# 03-Gate_Driver.net
KiCad netlist of a schematic drawn in Altium Designer
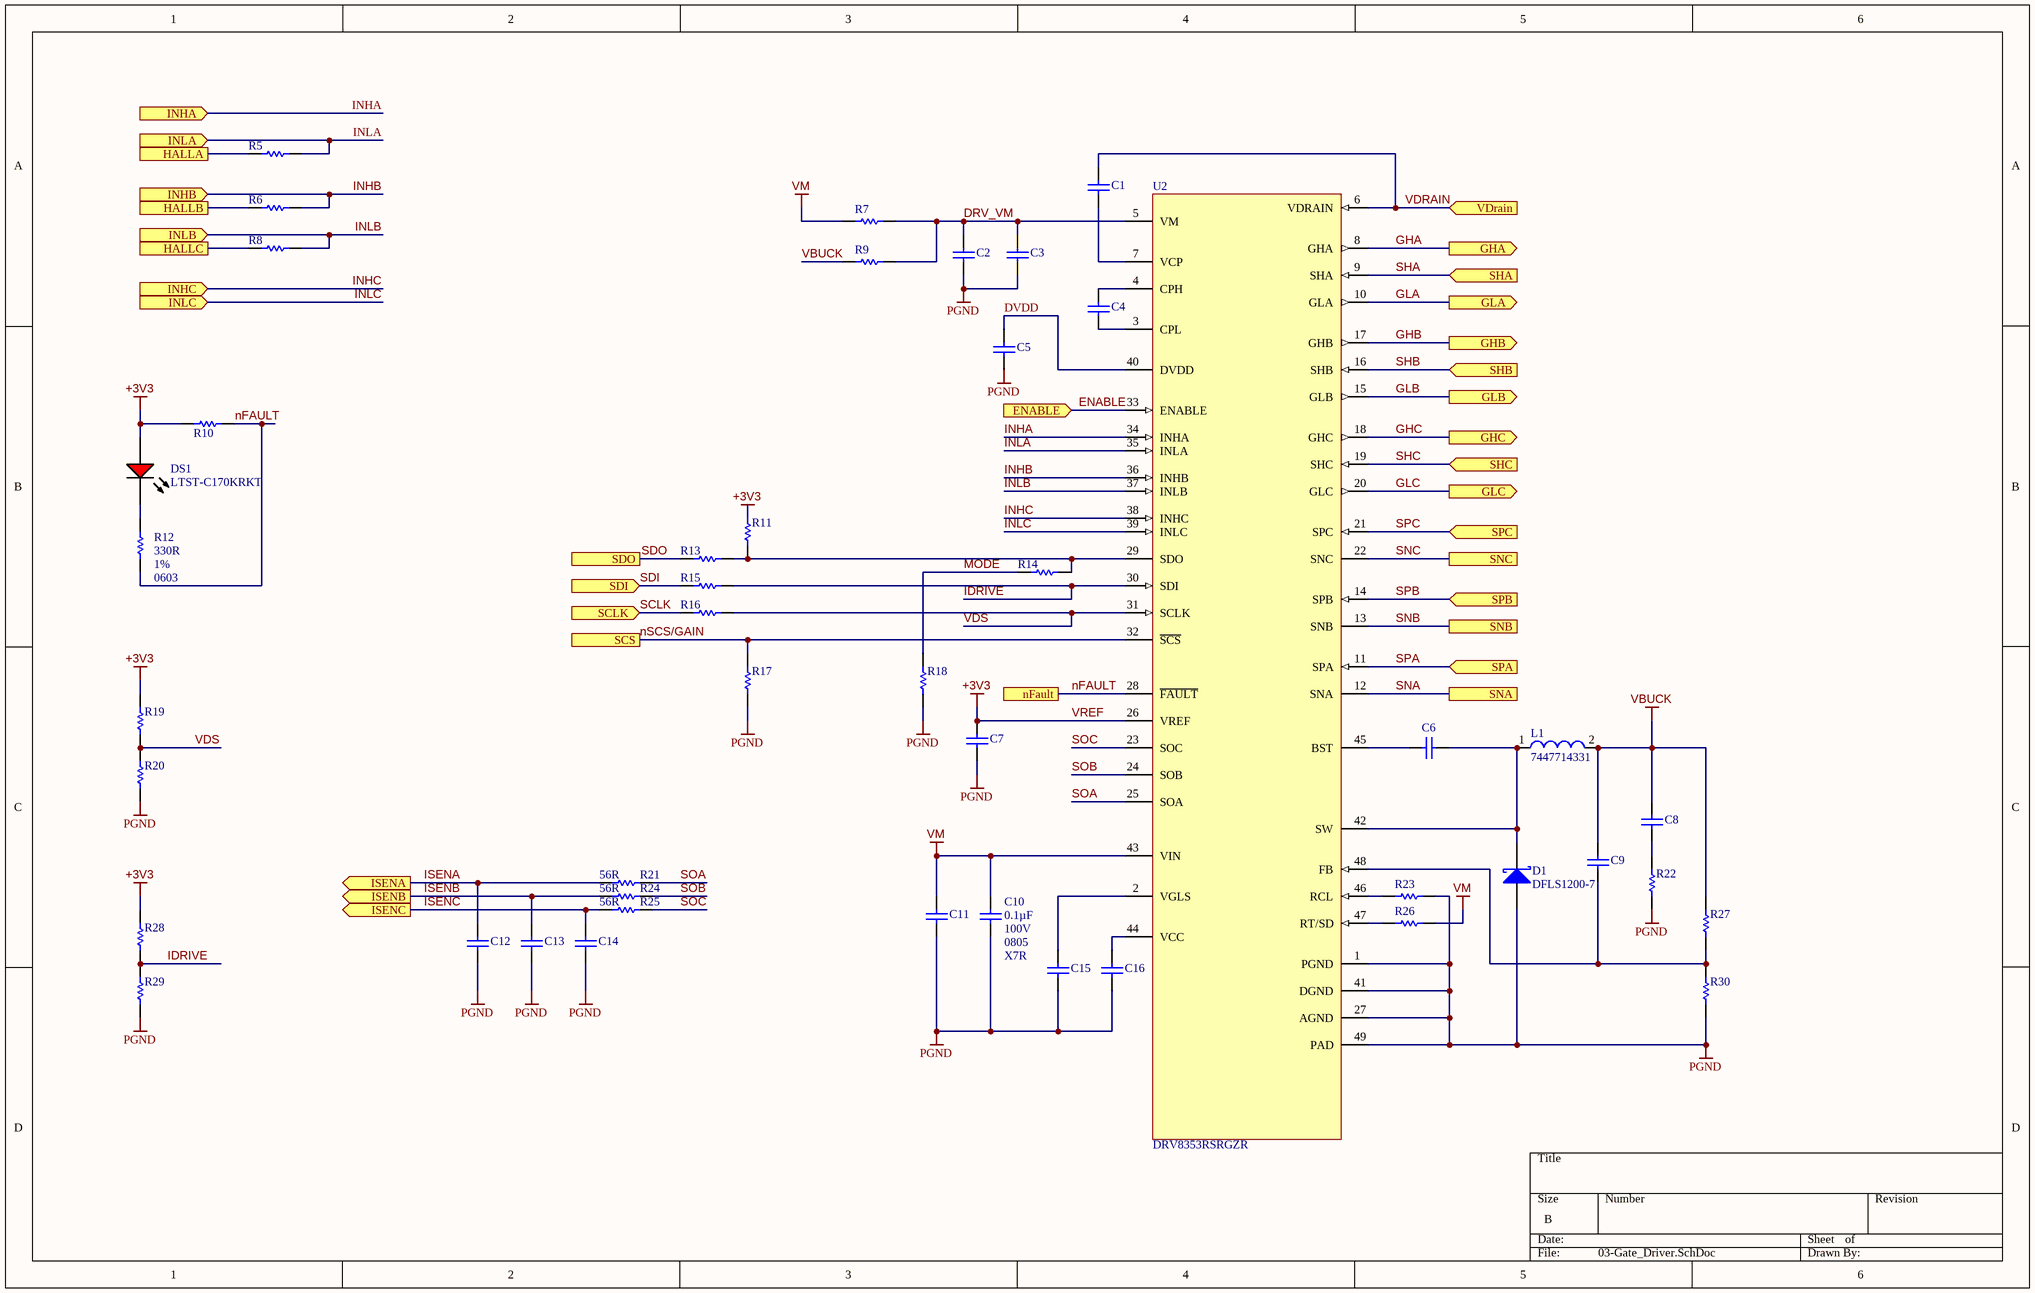
[diagram p0: 03-Gate_Driver.SchDoc]

(export (version "E")
  (design (tool "Eeschema 10.0.6"))
  (components
    (comp (ref "C1")
      (value "GRM31CR72A105KA01L")
      (footprint "CAPC3216X180X55ML20T25")
      (description "Chip Capacitor, 1 uF, +/- 10%, 100 V, -55 to 125 degC, 1206 (3216 Metric), RoHS, Tape and Reel")
      (fields (field (name "TOLERANCE") "±10%") (field (name "MANUFACTURER") "Murata"))
      (libsource (lib "Altium Content Vault") (part "CAP-NP-2"))
    )
    (comp (ref "C2")
      (value "C5750X7S2A106M230KB")
      (footprint "TDK-C5750-2_L")
      (description "Chip Capacitor, 10 uF, +/- 20%, 100 V, -55 to 125 degC, 2220 (5750 Metric), RoHS, Tape and Reel")
      (fields
        (field (name "PCN PART NUMBER") "MLCCPartNumberChange30/Nov/2012")
        (field (name "MANUFACTURER") "TDK")
      )
      (libsource (lib "Altium Content Vault") (part "CAP-NP-2"))
    )
    (comp (ref "C3")
      (value "C2012X7R2A104K125AA")
      (footprint "CAPC2013X145X20ML20")
      (description "Chip Capacitor, 100 nF, +/- 10%, 100 V, -55 to 1255 degC, 0805 (2012 Metric), RoHS, Tape and Reel")
      (fields (field (name "MANUFACTURER") "TDK") (field (name "TOLERANCE") "±10%"))
      (libsource (lib "Altium Content Vault") (part "CAP-NP-2"))
    )
    (comp (ref "C4")
      (value "C0805C473K1RACTU")
      (footprint "CAPC2013X110X50LL20T25")
      (fields (field (name "MANUFACTURER") "Kemet"))
      (libsource (lib "Altium Content Vault") (part "CAP"))
    )
    (comp (ref "C5")
      (value "C0603C105K4RACTU")
      (footprint "CAPC1608X90X35LL15T15")
      (fields (field (name "MANUFACTURER") "Kemet"))
      (libsource (lib "Altium Content Vault") (part "CAP"))
    )
    (comp (ref "C6")
      (value "C0603C103K4RACTU")
      (footprint "CAPC1608X87X35ML15T15")
      (fields (field (name "MANUFACTURER") "Kemet"))
      (libsource (lib "Altium Content Vault") (part "CAP"))
    )
    (comp (ref "C7")
      (value "C0603C104J4RACTU")
      (footprint "CAPC1608X87X35NL15T15")
      (fields (field (name "MANUFACTURER") "Kemet"))
      (libsource (lib "Altium Content Vault") (part "CAP"))
    )
    (comp (ref "C8")
      (value "C2012X7R1H225K125AC")
      (footprint "CAPC2013X145X20LL20")
      (description "Chip Capacitor, 2.2 uF, +/- 10%, 50 V, -55 to 125 degC, 0805 (2012 Metric), RoHS, Tape and Reel")
      (fields (field (name "MANUFACTURER") "TDK") (field (name "TOLERANCE") "±10%"))
      (libsource (lib "Altium Content Vault") (part "CAP-NP-2"))
    )
    (comp (ref "C9")
      (value "GRM1885C1H362JA01D")
      (footprint "CAPC1608X90X35ML10T15")
      (fields (field (name "MANUFACTURER") "Murata"))
      (libsource (lib "Altium Content Vault") (part "CAP"))
    )
    (comp (ref "C10")
      (value "C2012X7R2A104K125AA")
      (footprint "CAPC2013X145X20ML20")
      (description "Chip Capacitor, 100 nF, +/- 10%, 100 V, -55 to 1255 degC, 0805 (2012 Metric), RoHS, Tape and Reel")
      (fields
        (field (name "TEMPERATURE COEFFICIENT") "X7R")
        (field (name "MANUFACTURER") "TDK")
        (field (name "VOLTAGE - RATED") "100V")
        (field (name "TOLERANCE") "±10%")
        (field (name "PACKAGE REFERENCE") "0805")
        (field (name "CAPACITANCE") "0.1µF")
      )
      (libsource (lib "Altium Content Vault") (part "CAP-NP-2"))
    )
    (comp (ref "C11")
      (value "C3216X7R2A105K160AA")
      (footprint "CAPC3216X180X20LL20")
      (description "Chip Capacitor, 1 uF, +/- 10%, 100 V, -55 to 125 degC, 1206 (3216 Metric), RoHS, Tape and Reel")
      (fields (field (name "MANUFACTURER") "TDK") (field (name "TOLERANCE") "±10%"))
      (libsource (lib "Altium Content Vault") (part "CAP-NP-2"))
    )
    (comp (ref "C12")
      (value "GRM188R71C222KA01D")
      (footprint "CAPC1608X90X35NL10T15")
      (fields (field (name "MANUFACTURER") "Murata"))
      (libsource (lib "Altium Content Vault") (part "CAP"))
    )
    (comp (ref "C13")
      (value "GRM188R71C222KA01D")
      (footprint "CAPC1608X90X35NL10T15")
      (fields (field (name "MANUFACTURER") "Murata"))
      (libsource (lib "Altium Content Vault") (part "CAP"))
    )
    (comp (ref "C14")
      (value "GRM188R71C222KA01D")
      (footprint "CAPC1608X90X35NL10T15")
      (fields (field (name "MANUFACTURER") "Murata"))
      (libsource (lib "Altium Content Vault") (part "CAP"))
    )
    (comp (ref "C15")
      (value "C0805C105K3RACTU")
      (footprint "CAPC2013X140X50LL20T25")
      (fields (field (name "MANUFACTURER") "Kemet"))
      (libsource (lib "Altium Content Vault") (part "CAP"))
    )
    (comp (ref "C16")
      (value "C0603C105K4RACTU")
      (footprint "CAPC1608X90X35LL15T15")
      (fields (field (name "MANUFACTURER") "Kemet"))
      (libsource (lib "Altium Content Vault") (part "CAP"))
    )
    (comp (ref "D1")
      (value "DFLS1200-7")
      (footprint "DIOD-POWERDI123-2_A_V")
      (fields (field (name "MANUFACTURER") "Diodes Inc"))
      (libsource (lib "Altium Content Vault") (part "DSKY-AK-2"))
    )
    (comp (ref "DS1")
      (value "LTST-C170KRKT")
      (footprint "LTST-C170KRKT_V")
      (description "LED Red, 75 mW, 54 mcd, -55 to 85 degC, 2-Pin SMD, RoHS, Tape and Reel")
      (fields (field (name "MANUFACTURER") "Lite-On"))
      (libsource (lib "Altium Content Vault") (part "LED-RED-AK-2"))
    )
    (comp (ref "L1")
      (value "7447714331")
      (footprint "WE-PD 1050")
      (description "SMD-Shielded Power Inductor WE-PD, L=330 µH")
      (fields (field (name "MANUFACTURER") "Wuerth Elektronik"))
      (libsource (lib "Altium Content Vault") (part "PAS-IND-INDUCTOR-2"))
    )
    (comp (ref "R5")
      (value "ERJ-3GEY0R00V")
      (footprint "RESC1608X55X30NL15T15")
      (fields (field (name "MANUFACTURER") "Panasonic"))
      (libsource (lib "Altium Content Vault") (part "RES"))
    )
    (comp (ref "R6")
      (value "ERJ-3GEY0R00V")
      (footprint "RESC1608X55X30NL15T15")
      (fields (field (name "MANUFACTURER") "Panasonic"))
      (libsource (lib "Altium Content Vault") (part "RES"))
    )
    (comp (ref "R7")
      (value "ERJ-3GEY0R00V")
      (footprint "RESC1608X55X30NL15T15")
      (fields (field (name "MANUFACTURER") "Panasonic"))
      (libsource (lib "Altium Content Vault") (part "RES"))
    )
    (comp (ref "R8")
      (value "ERJ-3GEY0R00V")
      (footprint "RESC1608X55X30NL15T15")
      (fields (field (name "MANUFACTURER") "Panasonic"))
      (libsource (lib "Altium Content Vault") (part "RES"))
    )
    (comp (ref "R9")
      (value "ERJ-3GEY0R00V")
      (footprint "RESC1608X55X30NL15T15")
      (fields (field (name "MANUFACTURER") "Panasonic"))
      (libsource (lib "Altium Content Vault") (part "RES"))
    )
    (comp (ref "R10")
      (value "RG1608P-103-B-T5")
      (footprint "RESC1608X50X30NL20T20")
      (fields (field (name "MANUFACTURER") "Susumu"))
      (libsource (lib "Altium Content Vault") (part "RES"))
    )
    (comp (ref "R11")
      (value "ERJ-3GEYJ102V")
      (footprint "RESC1608X55X30ML15T15")
      (fields (field (name "MANUFACTURER") "Panasonic"))
      (libsource (lib "Altium Content Vault") (part "RES"))
    )
    (comp (ref "R12")
      (value "ERJ3EKF3300V")
      (footprint "RESC1608X55X30NL15T15")
      (fields
        (field (name "MANUFACTURER") "Panasonic")
        (field (name "CASE CODE (IMPERIAL)") "0603")
        (field (name "TOLERANCE") "1%")
        (field (name "RESISTANCE") "330R")
      )
      (libsource (lib "Altium Content Vault") (part "RES"))
    )
    (comp (ref "R13")
      (value "ERJ-3GEY0R00V")
      (footprint "RESC1608X55X30NL15T15")
      (fields (field (name "MANUFACTURER") "Panasonic"))
      (libsource (lib "Altium Content Vault") (part "RES"))
    )
    (comp (ref "R14")
      (value "ERJ-3GEY0R00V")
      (footprint "RESC1608X55X30NL15T15")
      (fields (field (name "MANUFACTURER") "Panasonic"))
      (libsource (lib "Altium Content Vault") (part "RES"))
    )
    (comp (ref "R15")
      (value "ERJ-3GEY0R00V")
      (footprint "RESC1608X55X30NL15T15")
      (fields (field (name "MANUFACTURER") "Panasonic"))
      (libsource (lib "Altium Content Vault") (part "RES"))
    )
    (comp (ref "R16")
      (value "ERJ-3GEY0R00V")
      (footprint "RESC1608X55X30NL15T15")
      (fields (field (name "MANUFACTURER") "Panasonic"))
      (libsource (lib "Altium Content Vault") (part "RES"))
    )
    (comp (ref "R17")
      (value "CRCW060347K0JNEA")
      (footprint "RESC1609X50X30ML10T20")
      (fields (field (name "MANUFACTURER") "Vishay Dale"))
      (libsource (lib "Altium Content Vault") (part "RES"))
    )
    (comp (ref "R18")
      (value "CRCW060347K0JNEA")
      (footprint "RESC1609X50X30ML10T20")
      (fields (field (name "MANUFACTURER") "Vishay Dale"))
      (libsource (lib "Altium Content Vault") (part "RES"))
    )
    (comp (ref "R19")
      (value "CRCW060375K0JNEA")
      (footprint "RESC1609X50X30ML10T20")
      (fields (field (name "MANUFACTURER") "Vishay Dale"))
      (libsource (lib "Altium Content Vault") (part "RES"))
    )
    (comp (ref "R20")
      (value "CRCW060375K0JNEA")
      (footprint "RESC1609X50X30ML10T20")
      (fields (field (name "MANUFACTURER") "Vishay Dale"))
      (libsource (lib "Altium Content Vault") (part "RES"))
    )
    (comp (ref "R21")
      (value "CRCW060356R0FKEA")
      (footprint "RESC1609X50X30ML10T20")
      (fields
        (field (name "MANUFACTURER") "Vishay Dale")
        (field (name "TOLERANCE") "1%")
        (field (name "RESISTANCE") "56R")
      )
      (libsource (lib "Altium Content Vault") (part "RES"))
    )
    (comp (ref "R22")
      (value "2R61 1% 0603(1608)")
      (footprint "RESC0603(1608)_N")
      (description "2R61 0.1W 1% 0603 (1608 Metric)  SMD")
      (fields (field (name "POWER") "0.1 W") (field (name "TOLERANCE") "1 %"))
      (libsource (lib "Altium Content Vault") (part "RES"))
    )
    (comp (ref "R23")
      (value "CRCW0603107KFKEA")
      (footprint "RESC1609X50X30LL10T20")
      (fields (field (name "MANUFACTURER") "Vishay Dale"))
      (libsource (lib "Altium Content Vault") (part "RES"))
    )
    (comp (ref "R24")
      (value "CRCW060356R0FKEA")
      (footprint "RESC1609X50X30ML10T20")
      (fields
        (field (name "MANUFACTURER") "Vishay Dale")
        (field (name "TOLERANCE") "1%")
        (field (name "RESISTANCE") "56R")
      )
      (libsource (lib "Altium Content Vault") (part "RES"))
    )
    (comp (ref "R25")
      (value "CRCW060356R0FKEA")
      (footprint "RESC1609X50X30ML10T20")
      (fields
        (field (name "MANUFACTURER") "Vishay Dale")
        (field (name "TOLERANCE") "1%")
        (field (name "RESISTANCE") "56R")
      )
      (libsource (lib "Altium Content Vault") (part "RES"))
    )
    (comp (ref "R26")
      (value "ERJ-3EKF2743V")
      (footprint "RESC1608X55X30NL15T15")
      (fields (field (name "MANUFACTURER") "Panasonic"))
      (libsource (lib "Altium Content Vault") (part "RES"))
    )
    (comp (ref "R27")
      (value "RG1608P-103-B-T5")
      (footprint "RESC1608X50X30NL20T20")
      (fields (field (name "MANUFACTURER") "Susumu"))
      (libsource (lib "Altium Content Vault") (part "RES"))
    )
    (comp (ref "R28")
      (value "CRCW060375K0JNEA")
      (footprint "RESC1609X50X30ML10T20")
      (fields (field (name "MANUFACTURER") "Vishay Dale"))
      (libsource (lib "Altium Content Vault") (part "RES"))
    )
    (comp (ref "R29")
      (value "CRCW060375K0JNEA")
      (footprint "RESC1609X50X30ML10T20")
      (fields (field (name "MANUFACTURER") "Vishay Dale"))
      (libsource (lib "Altium Content Vault") (part "RES"))
    )
    (comp (ref "R30")
      (value "RG1608P-2611-B-T5")
      (footprint "RESC1608X50X30NL20T20")
      (fields (field (name "MANUFACTURER") "Susumu"))
      (libsource (lib "Altium Content Vault") (part "RES"))
    )
    (comp (ref "U2")
      (value "DRV8353RSRGZR")
      (footprint "DRV8353RS")
      (libsource (lib "driver_board_lib") (part "DRV8353RSRGZR"))
    )
  )
  (nets
    (net (code "1") (name "+3V3") (class "Default")
      (node (ref "C7") (pin "2") (pinfunction "2_2") (pintype "passive"))
      (node (ref "DS1") (pin "1") (pinfunction "A_1") (pintype "passive"))
      (node (ref "R10") (pin "2") (pinfunction "2_2") (pintype "passive"))
      (node (ref "R11") (pin "2") (pinfunction "2_2") (pintype "passive"))
      (node (ref "R19") (pin "1") (pinfunction "1_1") (pintype "passive"))
      (node (ref "R28") (pin "1") (pinfunction "1_1") (pintype "passive"))
      (node (ref "U2") (pin "26") (pinfunction "VREF_26") (pintype "passive"))
    )
    (net (code "2") (name "/DRV_VM") (class "Default")
      (node (ref "C2") (pin "2") (pinfunction "2_2") (pintype "passive"))
      (node (ref "C3") (pin "2") (pinfunction "2_2") (pintype "passive"))
      (node (ref "R7") (pin "2") (pinfunction "2_2") (pintype "passive"))
      (node (ref "R9") (pin "2") (pinfunction "2_2") (pintype "passive"))
      (node (ref "U2") (pin "5") (pinfunction "VM_5") (pintype "power_in"))
    )
    (net (code "3") (name "/DVDD") (class "Default")
      (node (ref "C5") (pin "2") (pinfunction "2_2") (pintype "passive"))
      (node (ref "U2") (pin "40") (pinfunction "DVDD_40") (pintype "power_in"))
    )
    (net (code "4") (name "/ENABLE") (class "Default")
      (node (ref "U2") (pin "33") (pinfunction "ENABLE_33") (pintype "input"))
    )
    (net (code "5") (name "/GHA") (class "Default")
      (node (ref "U2") (pin "8") (pinfunction "GHA_8") (pintype "output"))
    )
    (net (code "6") (name "/GHB") (class "Default")
      (node (ref "U2") (pin "17") (pinfunction "GHB_17") (pintype "output"))
    )
    (net (code "7") (name "/GHC") (class "Default")
      (node (ref "U2") (pin "18") (pinfunction "GHC_18") (pintype "output"))
    )
    (net (code "8") (name "/GLA") (class "Default")
      (node (ref "U2") (pin "10") (pinfunction "GLA_10") (pintype "output"))
    )
    (net (code "9") (name "/GLB") (class "Default")
      (node (ref "U2") (pin "15") (pinfunction "GLB_15") (pintype "output"))
    )
    (net (code "10") (name "/GLC") (class "Default")
      (node (ref "U2") (pin "20") (pinfunction "GLC_20") (pintype "output"))
    )
    (net (code "11") (name "/HALLA") (class "Default")
      (node (ref "R5") (pin "1") (pinfunction "1_1") (pintype "passive"))
    )
    (net (code "12") (name "/HALLB") (class "Default")
      (node (ref "R6") (pin "1") (pinfunction "1_1") (pintype "passive"))
    )
    (net (code "13") (name "/HALLC") (class "Default")
      (node (ref "R8") (pin "1") (pinfunction "1_1") (pintype "passive"))
    )
    (net (code "14") (name "/IDRIVE") (class "Default")
      (node (ref "R15") (pin "2") (pinfunction "2_2") (pintype "passive"))
      (node (ref "R28") (pin "2") (pinfunction "2_2") (pintype "passive"))
      (node (ref "R29") (pin "1") (pinfunction "1_1") (pintype "passive"))
      (node (ref "U2") (pin "30") (pinfunction "SDI_30") (pintype "input"))
    )
    (net (code "15") (name "/INHA") (class "Default")
      (node (ref "U2") (pin "34") (pinfunction "INHA_34") (pintype "input"))
    )
    (net (code "16") (name "/INHB") (class "Default")
      (node (ref "R6") (pin "2") (pinfunction "2_2") (pintype "passive"))
      (node (ref "U2") (pin "36") (pinfunction "INHB_36") (pintype "input"))
    )
    (net (code "17") (name "/INHC") (class "Default")
      (node (ref "U2") (pin "38") (pinfunction "INHC_38") (pintype "input"))
    )
    (net (code "18") (name "/INLA") (class "Default")
      (node (ref "R5") (pin "2") (pinfunction "2_2") (pintype "passive"))
      (node (ref "U2") (pin "35") (pinfunction "INLA_35") (pintype "input"))
    )
    (net (code "19") (name "/INLB") (class "Default")
      (node (ref "R8") (pin "2") (pinfunction "2_2") (pintype "passive"))
      (node (ref "U2") (pin "37") (pinfunction "INLB_37") (pintype "input"))
    )
    (net (code "20") (name "/INLC") (class "Default")
      (node (ref "U2") (pin "39") (pinfunction "INLC_39") (pintype "input"))
    )
    (net (code "21") (name "/ISENA") (class "Default")
      (node (ref "C12") (pin "2") (pinfunction "2_2") (pintype "passive"))
      (node (ref "R21") (pin "1") (pinfunction "1_1") (pintype "passive"))
    )
    (net (code "22") (name "/ISENB") (class "Default")
      (node (ref "C13") (pin "2") (pinfunction "2_2") (pintype "passive"))
      (node (ref "R24") (pin "1") (pinfunction "1_1") (pintype "passive"))
    )
    (net (code "23") (name "/ISENC") (class "Default")
      (node (ref "C14") (pin "2") (pinfunction "2_2") (pintype "passive"))
      (node (ref "R25") (pin "1") (pinfunction "1_1") (pintype "passive"))
    )
    (net (code "24") (name "/MODE") (class "Default")
      (node (ref "R14") (pin "1") (pinfunction "1_1") (pintype "passive"))
      (node (ref "R18") (pin "2") (pinfunction "2_2") (pintype "passive"))
    )
    (net (code "25") (name "/SCLK") (class "Default")
      (node (ref "R16") (pin "1") (pinfunction "1_1") (pintype "passive"))
    )
    (net (code "26") (name "/SDI") (class "Default")
      (node (ref "R15") (pin "1") (pinfunction "1_1") (pintype "passive"))
    )
    (net (code "27") (name "/SDO") (class "Default")
      (node (ref "R13") (pin "1") (pinfunction "1_1") (pintype "passive"))
    )
    (net (code "28") (name "/SHA") (class "Default")
      (node (ref "U2") (pin "9") (pinfunction "SHA_9") (pintype "input"))
    )
    (net (code "29") (name "/SHB") (class "Default")
      (node (ref "U2") (pin "16") (pinfunction "SHB_16") (pintype "input"))
    )
    (net (code "30") (name "/SHC") (class "Default")
      (node (ref "U2") (pin "19") (pinfunction "SHC_19") (pintype "input"))
    )
    (net (code "31") (name "/SNA") (class "Default")
      (node (ref "U2") (pin "12") (pinfunction "SNA_12") (pintype "passive"))
    )
    (net (code "32") (name "/SNB") (class "Default")
      (node (ref "U2") (pin "13") (pinfunction "SNB_13") (pintype "passive"))
    )
    (net (code "33") (name "/SNC") (class "Default")
      (node (ref "U2") (pin "22") (pinfunction "SNC_22") (pintype "passive"))
    )
    (net (code "34") (name "/SOA") (class "Default")
      (node (ref "R21") (pin "2") (pinfunction "2_2") (pintype "passive"))
      (node (ref "U2") (pin "25") (pinfunction "SOA_25") (pintype "passive"))
    )
    (net (code "35") (name "/SOB") (class "Default")
      (node (ref "R24") (pin "2") (pinfunction "2_2") (pintype "passive"))
      (node (ref "U2") (pin "24") (pinfunction "SOB_24") (pintype "passive"))
    )
    (net (code "36") (name "/SOC") (class "Default")
      (node (ref "R25") (pin "2") (pinfunction "2_2") (pintype "passive"))
      (node (ref "U2") (pin "23") (pinfunction "SOC_23") (pintype "passive"))
    )
    (net (code "37") (name "/SPA") (class "Default")
      (node (ref "U2") (pin "11") (pinfunction "SPA_11") (pintype "input"))
    )
    (net (code "38") (name "/SPB") (class "Default")
      (node (ref "U2") (pin "14") (pinfunction "SPB_14") (pintype "input"))
    )
    (net (code "39") (name "/SPC") (class "Default")
      (node (ref "U2") (pin "21") (pinfunction "SPC_21") (pintype "input"))
    )
    (net (code "40") (name "/VDRAIN") (class "Default")
      (node (ref "C1") (pin "2") (pinfunction "2_2") (pintype "passive"))
      (node (ref "U2") (pin "6") (pinfunction "VDRAIN_6") (pintype "input"))
    )
    (net (code "41") (name "/VDS") (class "Default")
      (node (ref "R16") (pin "2") (pinfunction "2_2") (pintype "passive"))
      (node (ref "R19") (pin "2") (pinfunction "2_2") (pintype "passive"))
      (node (ref "R20") (pin "1") (pinfunction "1_1") (pintype "passive"))
      (node (ref "U2") (pin "31") (pinfunction "SCLK_31") (pintype "input"))
    )
    (net (code "42") (name "/nFAULT") (class "Default")
      (node (ref "R10") (pin "1") (pinfunction "1_1") (pintype "passive"))
      (node (ref "R12") (pin "1") (pinfunction "1_1") (pintype "passive"))
      (node (ref "U2") (pin "28") (pinfunction "FAULT_28") (pintype "open_collector"))
    )
    (net (code "43") (name "/nSCS{slash}GAIN") (class "Default")
      (node (ref "R17") (pin "2") (pinfunction "2_2") (pintype "passive"))
      (node (ref "U2") (pin "32") (pinfunction "SCS_32") (pintype "passive"))
    )
    (net (code "44") (name "Net-(C8-Pad1)") (class "Default")
      (node (ref "C8") (pin "1") (pinfunction "1_1") (pintype "passive"))
      (node (ref "R22") (pin "2") (pinfunction "2_2") (pintype "passive"))
    )
    (net (code "45") (name "Net-(D1-K)") (class "Default")
      (node (ref "C6") (pin "2") (pinfunction "2_2") (pintype "passive"))
      (node (ref "D1") (pin "2") (pinfunction "K_2") (pintype "passive"))
      (node (ref "L1") (pin "1") (pinfunction "1_1") (pintype "passive"))
      (node (ref "U2") (pin "42") (pinfunction "SW_42") (pintype "power_in"))
    )
    (net (code "46") (name "Net-(DS1-K)") (class "Default")
      (node (ref "DS1") (pin "2") (pinfunction "K_2") (pintype "passive"))
      (node (ref "R12") (pin "2") (pinfunction "2_2") (pintype "passive"))
    )
    (net (code "47") (name "Net-(U2-BST)") (class "Default")
      (node (ref "C6") (pin "1") (pinfunction "1_1") (pintype "passive"))
      (node (ref "U2") (pin "45") (pinfunction "BST_45") (pintype "power_in"))
    )
    (net (code "48") (name "Net-(U2-CPH)") (class "Default")
      (node (ref "C4") (pin "2") (pinfunction "2_2") (pintype "passive"))
      (node (ref "U2") (pin "4") (pinfunction "CPH_4") (pintype "passive"))
    )
    (net (code "49") (name "Net-(U2-CPL)") (class "Default")
      (node (ref "C4") (pin "1") (pinfunction "1_1") (pintype "passive"))
      (node (ref "U2") (pin "3") (pinfunction "CPL_3") (pintype "passive"))
    )
    (net (code "50") (name "Net-(U2-FB)") (class "Default")
      (node (ref "C9") (pin "1") (pinfunction "1_1") (pintype "passive"))
      (node (ref "R27") (pin "1") (pinfunction "1_1") (pintype "passive"))
      (node (ref "R30") (pin "2") (pinfunction "2_2") (pintype "passive"))
      (node (ref "U2") (pin "48") (pinfunction "FB_48") (pintype "input"))
    )
    (net (code "51") (name "Net-(U2-RCL)") (class "Default")
      (node (ref "R23") (pin "1") (pinfunction "1_1") (pintype "passive"))
      (node (ref "U2") (pin "46") (pinfunction "RCL_46") (pintype "input"))
    )
    (net (code "52") (name "Net-(U2-RT{slash}SD)") (class "Default")
      (node (ref "R26") (pin "1") (pinfunction "1_1") (pintype "passive"))
      (node (ref "U2") (pin "47") (pinfunction "RT/SD_47") (pintype "input"))
    )
    (net (code "53") (name "Net-(U2-SDO)") (class "Default")
      (node (ref "R11") (pin "1") (pinfunction "1_1") (pintype "passive"))
      (node (ref "R13") (pin "2") (pinfunction "2_2") (pintype "passive"))
      (node (ref "R14") (pin "2") (pinfunction "2_2") (pintype "passive"))
      (node (ref "U2") (pin "29") (pinfunction "SDO_29") (pintype "passive"))
    )
    (net (code "54") (name "Net-(U2-VCC)") (class "Default")
      (node (ref "C16") (pin "2") (pinfunction "2_2") (pintype "passive"))
      (node (ref "U2") (pin "44") (pinfunction "VCC_44") (pintype "power_in"))
    )
    (net (code "55") (name "Net-(U2-VCP)") (class "Default")
      (node (ref "C1") (pin "1") (pinfunction "1_1") (pintype "passive"))
      (node (ref "U2") (pin "7") (pinfunction "VCP_7") (pintype "power_in"))
    )
    (net (code "56") (name "Net-(U2-VGLS)") (class "Default")
      (node (ref "C15") (pin "2") (pinfunction "2_2") (pintype "passive"))
      (node (ref "U2") (pin "2") (pinfunction "VGLS_2") (pintype "power_in"))
    )
    (net (code "57") (name "PGND") (class "Default")
      (node (ref "C10") (pin "1") (pinfunction "1_1") (pintype "passive"))
      (node (ref "C11") (pin "1") (pinfunction "1_1") (pintype "passive"))
      (node (ref "C12") (pin "1") (pinfunction "1_1") (pintype "passive"))
      (node (ref "C13") (pin "1") (pinfunction "1_1") (pintype "passive"))
      (node (ref "C14") (pin "1") (pinfunction "1_1") (pintype "passive"))
      (node (ref "C15") (pin "1") (pinfunction "1_1") (pintype "passive"))
      (node (ref "C16") (pin "1") (pinfunction "1_1") (pintype "passive"))
      (node (ref "C2") (pin "1") (pinfunction "1_1") (pintype "passive"))
      (node (ref "C3") (pin "1") (pinfunction "1_1") (pintype "passive"))
      (node (ref "C5") (pin "1") (pinfunction "1_1") (pintype "passive"))
      (node (ref "C7") (pin "1") (pinfunction "1_1") (pintype "passive"))
      (node (ref "D1") (pin "1") (pinfunction "A_1") (pintype "passive"))
      (node (ref "R17") (pin "1") (pinfunction "1_1") (pintype "passive"))
      (node (ref "R18") (pin "1") (pinfunction "1_1") (pintype "passive"))
      (node (ref "R20") (pin "2") (pinfunction "2_2") (pintype "passive"))
      (node (ref "R22") (pin "1") (pinfunction "1_1") (pintype "passive"))
      (node (ref "R23") (pin "2") (pinfunction "2_2") (pintype "passive"))
      (node (ref "R29") (pin "2") (pinfunction "2_2") (pintype "passive"))
      (node (ref "R30") (pin "1") (pinfunction "1_1") (pintype "passive"))
      (node (ref "U2") (pin "1") (pinfunction "PGND_1") (pintype "power_in"))
      (node (ref "U2") (pin "27") (pinfunction "AGND_27") (pintype "power_in"))
      (node (ref "U2") (pin "41") (pinfunction "DGND_41") (pintype "power_in"))
      (node (ref "U2") (pin "49") (pinfunction "PAD_49") (pintype "power_in"))
    )
    (net (code "58") (name "VBUCK") (class "Default")
      (node (ref "C8") (pin "2") (pinfunction "2_2") (pintype "passive"))
      (node (ref "C9") (pin "2") (pinfunction "2_2") (pintype "passive"))
      (node (ref "L1") (pin "2") (pinfunction "2_2") (pintype "passive"))
      (node (ref "R27") (pin "2") (pinfunction "2_2") (pintype "passive"))
      (node (ref "R9") (pin "1") (pinfunction "1_1") (pintype "passive"))
    )
    (net (code "59") (name "VM") (class "Default")
      (node (ref "C10") (pin "2") (pinfunction "2_2") (pintype "passive"))
      (node (ref "C11") (pin "2") (pinfunction "2_2") (pintype "passive"))
      (node (ref "R26") (pin "2") (pinfunction "2_2") (pintype "passive"))
      (node (ref "R7") (pin "1") (pinfunction "1_1") (pintype "passive"))
      (node (ref "U2") (pin "43") (pinfunction "VIN_43") (pintype "power_in"))
    )
  )
)
